# boardBase2.net
KiCad netlist of a schematic drawn in EAGLE
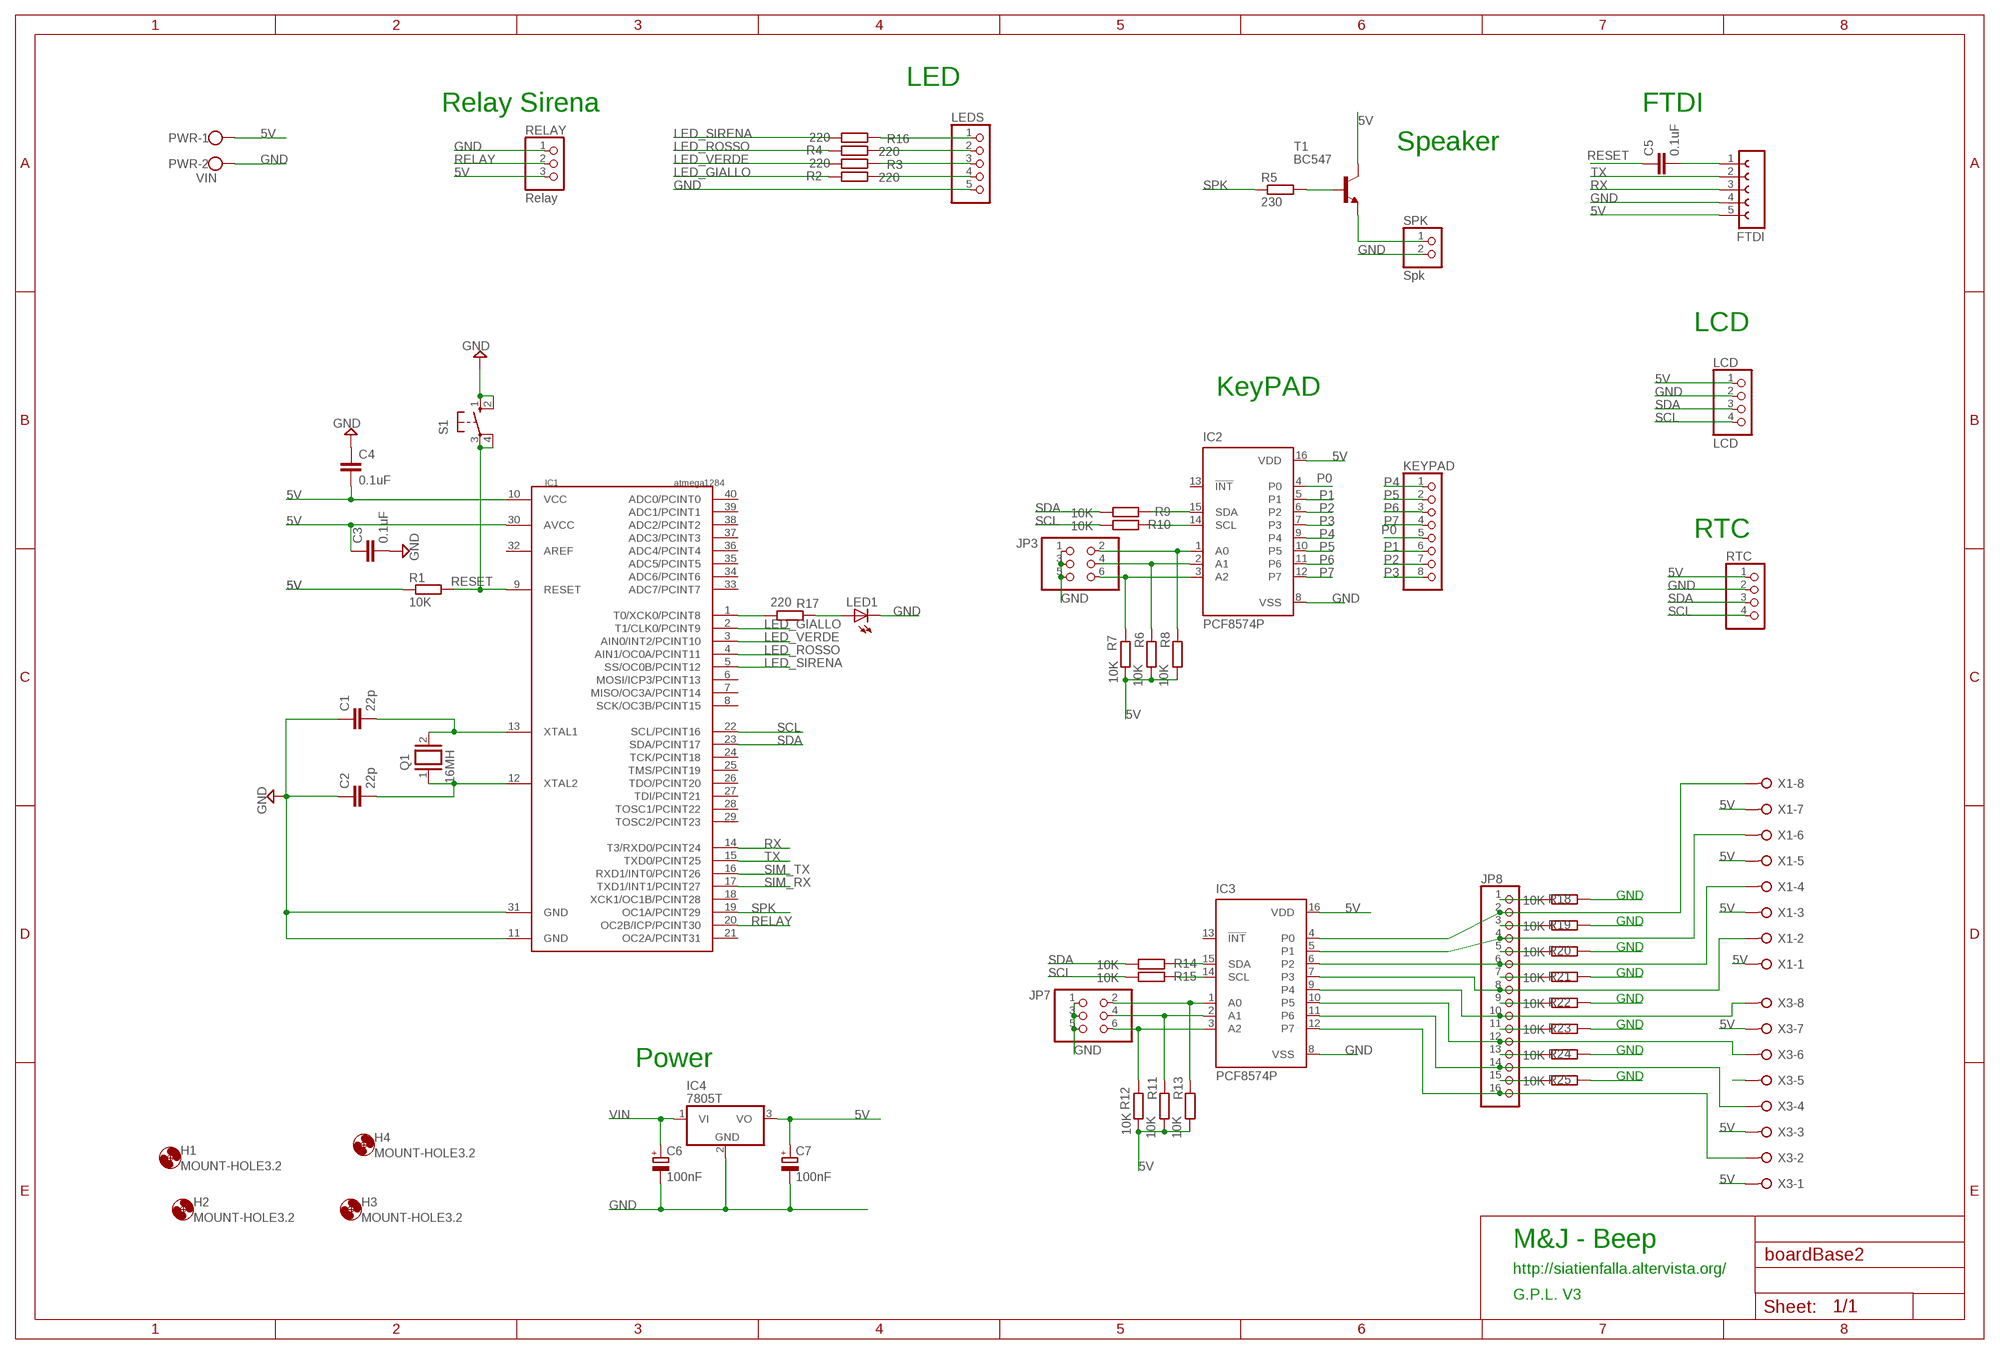
[diagram p0: schematic, sheet 1]

(export (version "E")
  (design (tool "Eeschema 10.0.6"))
  (components
    (comp (ref "C1")
      (value "22p")
      (footprint "eagle-import:C025-024X044")
      (libsource (lib "eagle-import") (part "C-EU025-024X044"))
    )
    (comp (ref "C2")
      (value "22p")
      (footprint "eagle-import:C025-024X044")
      (libsource (lib "eagle-import") (part "C-EU025-024X044"))
    )
    (comp (ref "C3")
      (value "0.1uF")
      (footprint "eagle-import:C025-025X050")
      (libsource (lib "eagle-import") (part "C-EU025-025X050"))
    )
    (comp (ref "C4")
      (value "0.1uF")
      (footprint "eagle-import:C025-025X050")
      (libsource (lib "eagle-import") (part "C-EU025-025X050"))
    )
    (comp (ref "C5")
      (value "0.1uF")
      (footprint "eagle-import:C025-025X050")
      (libsource (lib "eagle-import") (part "C-EU025-025X050"))
    )
    (comp (ref "C6")
      (value "100nF")
      (footprint "eagle-import:E3,5-10")
      (libsource (lib "eagle-import") (part "CPOL-EUE3.5-10"))
    )
    (comp (ref "C7")
      (value "100nF")
      (footprint "eagle-import:E3,5-10")
      (libsource (lib "eagle-import") (part "CPOL-EUE3.5-10"))
    )
    (comp (ref "FTDI")
      (value "FE05-1")
      (footprint "eagle-import:FE05-1")
      (libsource (lib "eagle-import") (part "FE05-1"))
    )
    (comp (ref "H1")
      (value "MOUNT-HOLE3.2")
      (footprint "eagle-import:3,2")
      (libsource (lib "eagle-import") (part "MOUNT-HOLE3.2"))
    )
    (comp (ref "H2")
      (value "MOUNT-HOLE3.2")
      (footprint "eagle-import:3,2")
      (libsource (lib "eagle-import") (part "MOUNT-HOLE3.2"))
    )
    (comp (ref "H3")
      (value "MOUNT-HOLE3.2")
      (footprint "eagle-import:3,2")
      (libsource (lib "eagle-import") (part "MOUNT-HOLE3.2"))
    )
    (comp (ref "H4")
      (value "MOUNT-HOLE3.2")
      (footprint "eagle-import:3,2")
      (libsource (lib "eagle-import") (part "MOUNT-HOLE3.2"))
    )
    (comp (ref "IC1")
      (value "atmega1284")
      (footprint "eagle-import:DIL40")
      (libsource (lib "eagle-import") (part "MEGA1284P"))
    )
    (comp (ref "IC2")
      (value "PCF8574P")
      (footprint "eagle-import:DIL16")
      (fields (field (name "MPN") "PCF8574PN"))
      (libsource (lib "eagle-import") (part "PCF8574P"))
    )
    (comp (ref "IC3")
      (value "PCF8574P")
      (footprint "eagle-import:DIL16")
      (fields (field (name "MPN") "PCF8574PN"))
      (libsource (lib "eagle-import") (part "PCF8574P"))
    )
    (comp (ref "IC4")
      (value "7805T")
      (footprint "eagle-import:TO220H")
      (libsource (lib "eagle-import") (part "78T05"))
    )
    (comp (ref "JP3")
      (value "PINHD-2X3")
      (footprint "eagle-import:2X03")
      (libsource (lib "eagle-import") (part "PINHD-2X3"))
    )
    (comp (ref "JP7")
      (value "PINHD-2X3")
      (footprint "eagle-import:2X03")
      (libsource (lib "eagle-import") (part "PINHD-2X3"))
    )
    (comp (ref "JP8")
      (value "PINHD-1X16")
      (footprint "eagle-import:1X16")
      (libsource (lib "eagle-import") (part "PINHD-1X16"))
    )
    (comp (ref "KEYPAD")
      (value "PINHD-1X8")
      (footprint "eagle-import:1X08")
      (libsource (lib "eagle-import") (part "PINHD-1X8"))
    )
    (comp (ref "LCD")
      (value "LCD")
      (footprint "eagle-import:1X04")
      (libsource (lib "eagle-import") (part "PINHD-1X4"))
    )
    (comp (ref "LED1")
      (value "LED3MM")
      (footprint "eagle-import:LED3MM")
      (libsource (lib "eagle-import") (part "LED3MM"))
    )
    (comp (ref "LEDS")
      (value "PINHD-1X5")
      (footprint "eagle-import:1X05")
      (libsource (lib "eagle-import") (part "PINHD-1X5"))
    )
    (comp (ref "PWR")
      (value "VIN")
      (footprint "eagle-import:W237-102")
      (fields (field (name "MPN") "237-102"))
      (libsource (lib "eagle-import") (part "W237-102"))
    )
    (comp (ref "Q1")
      (value "16MH")
      (footprint "eagle-import:QS")
      (libsource (lib "eagle-import") (part "XTAL/S"))
    )
    (comp (ref "R1")
      (value "10K")
      (footprint "eagle-import:0207_10")
      (libsource (lib "eagle-import") (part "R-EU_0207/10"))
    )
    (comp (ref "R2")
      (value "220")
      (footprint "eagle-import:0207_2V")
      (libsource (lib "eagle-import") (part "R-EU_0207/2V"))
    )
    (comp (ref "R3")
      (value "220")
      (footprint "eagle-import:0207_2V")
      (libsource (lib "eagle-import") (part "R-EU_0207/2V"))
    )
    (comp (ref "R4")
      (value "220")
      (footprint "eagle-import:0207_2V")
      (libsource (lib "eagle-import") (part "R-EU_0207/2V"))
    )
    (comp (ref "R5")
      (value "230")
      (footprint "eagle-import:0207_10")
      (libsource (lib "eagle-import") (part "R-EU_0207/10"))
    )
    (comp (ref "R6")
      (value "10K")
      (footprint "eagle-import:0207_10")
      (libsource (lib "eagle-import") (part "R-EU_0207/10"))
    )
    (comp (ref "R7")
      (value "10K")
      (footprint "eagle-import:0207_10")
      (libsource (lib "eagle-import") (part "R-EU_0207/10"))
    )
    (comp (ref "R8")
      (value "10K")
      (footprint "eagle-import:0207_10")
      (libsource (lib "eagle-import") (part "R-EU_0207/10"))
    )
    (comp (ref "R9")
      (value "10K")
      (footprint "eagle-import:0207_10")
      (libsource (lib "eagle-import") (part "R-EU_0207/10"))
    )
    (comp (ref "R10")
      (value "10K")
      (footprint "eagle-import:0207_10")
      (libsource (lib "eagle-import") (part "R-EU_0207/10"))
    )
    (comp (ref "R11")
      (value "10K")
      (footprint "eagle-import:0207_2V")
      (libsource (lib "eagle-import") (part "R-EU_0207/2V"))
    )
    (comp (ref "R12")
      (value "10K")
      (footprint "eagle-import:0207_2V")
      (libsource (lib "eagle-import") (part "R-EU_0207/2V"))
    )
    (comp (ref "R13")
      (value "10K")
      (footprint "eagle-import:0207_2V")
      (libsource (lib "eagle-import") (part "R-EU_0207/2V"))
    )
    (comp (ref "R14")
      (value "10K")
      (footprint "eagle-import:0207_2V")
      (libsource (lib "eagle-import") (part "R-EU_0207/2V"))
    )
    (comp (ref "R15")
      (value "10K")
      (footprint "eagle-import:0207_2V")
      (libsource (lib "eagle-import") (part "R-EU_0207/2V"))
    )
    (comp (ref "R16")
      (value "220")
      (footprint "eagle-import:0207_2V")
      (libsource (lib "eagle-import") (part "R-EU_0207/2V"))
    )
    (comp (ref "R17")
      (value "220")
      (footprint "eagle-import:0207_2V")
      (libsource (lib "eagle-import") (part "R-EU_0207/2V"))
    )
    (comp (ref "R18")
      (value "10K")
      (footprint "eagle-import:0207_2V")
      (libsource (lib "eagle-import") (part "R-EU_0207/2V"))
    )
    (comp (ref "R19")
      (value "10K")
      (footprint "eagle-import:0207_2V")
      (libsource (lib "eagle-import") (part "R-EU_0207/2V"))
    )
    (comp (ref "R20")
      (value "10K")
      (footprint "eagle-import:0207_2V")
      (libsource (lib "eagle-import") (part "R-EU_0207/2V"))
    )
    (comp (ref "R21")
      (value "10K")
      (footprint "eagle-import:0207_2V")
      (libsource (lib "eagle-import") (part "R-EU_0207/2V"))
    )
    (comp (ref "R22")
      (value "10K")
      (footprint "eagle-import:0207_2V")
      (libsource (lib "eagle-import") (part "R-EU_0207/2V"))
    )
    (comp (ref "R23")
      (value "10K")
      (footprint "eagle-import:0207_2V")
      (libsource (lib "eagle-import") (part "R-EU_0207/2V"))
    )
    (comp (ref "R24")
      (value "10K")
      (footprint "eagle-import:0207_2V")
      (libsource (lib "eagle-import") (part "R-EU_0207/2V"))
    )
    (comp (ref "R25")
      (value "10K")
      (footprint "eagle-import:0207_2V")
      (libsource (lib "eagle-import") (part "R-EU_0207/2V"))
    )
    (comp (ref "RELAY")
      (value "Relay")
      (footprint "eagle-import:1X03")
      (libsource (lib "eagle-import") (part "PINHD-1X3"))
    )
    (comp (ref "RTC")
      (value "PINHD-1X4")
      (footprint "eagle-import:1X04")
      (libsource (lib "eagle-import") (part "PINHD-1X4"))
    )
    (comp (ref "S1")
      (value "10-XX")
      (footprint "eagle-import:B3F-10XX")
      (fields (field (name "MPN") "B3F-1000"))
      (libsource (lib "eagle-import") (part "10-XX"))
    )
    (comp (ref "SPK")
      (value "Spk")
      (footprint "eagle-import:1X02")
      (libsource (lib "eagle-import") (part "PINHD-1X2"))
    )
    (comp (ref "T1")
      (value "BC547")
      (footprint "eagle-import:TO92")
      (libsource (lib "eagle-import") (part "BC547"))
    )
    (comp (ref "X1")
      (value "W237-08P")
      (footprint "eagle-import:W237-8P")
      (libsource (lib "eagle-import") (part "W237-08P"))
    )
    (comp (ref "X3")
      (value "W237-08P")
      (footprint "eagle-import:W237-8P")
      (libsource (lib "eagle-import") (part "W237-08P"))
    )
  )
  (nets
    (net (code "1") (name "/5V") (class "Default")
      (node (ref "C3") (pin "1") (pinfunction "1_1") (pintype "passive"))
      (node (ref "C4") (pin "2") (pinfunction "2_2") (pintype "passive"))
      (node (ref "C7") (pin "+") (pinfunction "+_+") (pintype "passive"))
      (node (ref "FTDI") (pin "5") (pinfunction "5_5") (pintype "passive"))
      (node (ref "IC1") (pin "10") (pinfunction "VCC_10") (pintype "bidirectional"))
      (node (ref "IC1") (pin "30") (pinfunction "AVCC_30") (pintype "bidirectional"))
      (node (ref "IC2") (pin "16") (pinfunction "VDD_16") (pintype "power_in"))
      (node (ref "IC3") (pin "16") (pinfunction "VDD_16") (pintype "power_in"))
      (node (ref "IC4") (pin "3") (pinfunction "VO_3") (pintype "passive"))
      (node (ref "LCD") (pin "1") (pinfunction "1_1") (pintype "passive"))
      (node (ref "PWR") (pin "1") (pinfunction "KL_1") (pintype "passive"))
      (node (ref "R1") (pin "1") (pinfunction "1_1") (pintype "passive"))
      (node (ref "R11") (pin "1") (pinfunction "1_1") (pintype "passive"))
      (node (ref "R12") (pin "2") (pinfunction "2_2") (pintype "passive"))
      (node (ref "R13") (pin "1") (pinfunction "1_1") (pintype "passive"))
      (node (ref "R6") (pin "1") (pinfunction "1_1") (pintype "passive"))
      (node (ref "R7") (pin "2") (pinfunction "2_2") (pintype "passive"))
      (node (ref "R8") (pin "1") (pinfunction "1_1") (pintype "passive"))
      (node (ref "RELAY") (pin "3") (pinfunction "3_3") (pintype "passive"))
      (node (ref "RTC") (pin "1") (pinfunction "1_1") (pintype "passive"))
      (node (ref "T1") (pin "3") (pinfunction "C_3") (pintype "passive"))
      (node (ref "X1") (pin "1") (pinfunction "KL_1") (pintype "passive"))
      (node (ref "X1") (pin "3") (pinfunction "KL_3") (pintype "passive"))
      (node (ref "X1") (pin "5") (pinfunction "KL_5") (pintype "passive"))
      (node (ref "X1") (pin "7") (pinfunction "KL_7") (pintype "passive"))
      (node (ref "X3") (pin "1") (pinfunction "KL_1") (pintype "passive"))
      (node (ref "X3") (pin "3") (pinfunction "KL_3") (pintype "passive"))
      (node (ref "X3") (pin "5") (pinfunction "KL_5") (pintype "passive"))
      (node (ref "X3") (pin "7") (pinfunction "KL_7") (pintype "passive"))
    )
    (net (code "2") (name "/LED_GIALLO") (class "Default")
      (node (ref "IC1") (pin "2") (pinfunction "T1/CLK0/PCINT9_2") (pintype "bidirectional"))
      (node (ref "R2") (pin "2") (pinfunction "2_2") (pintype "passive"))
    )
    (net (code "3") (name "/LED_ROSSO") (class "Default")
      (node (ref "IC1") (pin "4") (pinfunction "AIN1/OC0A/PCINT11_4") (pintype "bidirectional"))
      (node (ref "R4") (pin "2") (pinfunction "2_2") (pintype "passive"))
    )
    (net (code "4") (name "/LED_SIRENA") (class "Default")
      (node (ref "IC1") (pin "5") (pinfunction "SS/OC0B/PCINT12_5") (pintype "bidirectional"))
      (node (ref "R16") (pin "1") (pinfunction "1_1") (pintype "passive"))
    )
    (net (code "5") (name "/LED_VERDE") (class "Default")
      (node (ref "IC1") (pin "3") (pinfunction "AIN0/INT2/PCINT10_3") (pintype "bidirectional"))
      (node (ref "R3") (pin "1") (pinfunction "1_1") (pintype "passive"))
    )
    (net (code "6") (name "/P0") (class "Default")
      (node (ref "IC2") (pin "4") (pinfunction "P0_4") (pintype "bidirectional"))
      (node (ref "KEYPAD") (pin "5") (pinfunction "5_5") (pintype "passive"))
    )
    (net (code "7") (name "/P1") (class "Default")
      (node (ref "IC2") (pin "5") (pinfunction "P1_5") (pintype "bidirectional"))
      (node (ref "KEYPAD") (pin "6") (pinfunction "6_6") (pintype "passive"))
    )
    (net (code "8") (name "/P2") (class "Default")
      (node (ref "IC2") (pin "6") (pinfunction "P2_6") (pintype "bidirectional"))
      (node (ref "KEYPAD") (pin "7") (pinfunction "7_7") (pintype "passive"))
    )
    (net (code "9") (name "/P3") (class "Default")
      (node (ref "IC2") (pin "7") (pinfunction "P3_7") (pintype "bidirectional"))
      (node (ref "KEYPAD") (pin "8") (pinfunction "8_8") (pintype "passive"))
    )
    (net (code "10") (name "/P4") (class "Default")
      (node (ref "IC2") (pin "9") (pinfunction "P4_9") (pintype "bidirectional"))
      (node (ref "KEYPAD") (pin "1") (pinfunction "1_1") (pintype "passive"))
    )
    (net (code "11") (name "/P5") (class "Default")
      (node (ref "IC2") (pin "10") (pinfunction "P5_10") (pintype "bidirectional"))
      (node (ref "KEYPAD") (pin "2") (pinfunction "2_2") (pintype "passive"))
    )
    (net (code "12") (name "/P6") (class "Default")
      (node (ref "IC2") (pin "11") (pinfunction "P6_11") (pintype "bidirectional"))
      (node (ref "KEYPAD") (pin "3") (pinfunction "3_3") (pintype "passive"))
    )
    (net (code "13") (name "/P7") (class "Default")
      (node (ref "IC2") (pin "12") (pinfunction "P7_12") (pintype "bidirectional"))
      (node (ref "KEYPAD") (pin "4") (pinfunction "4_4") (pintype "passive"))
    )
    (net (code "14") (name "/RELAY") (class "Default")
      (node (ref "IC1") (pin "20") (pinfunction "OC2B/ICP/PCINT30_20") (pintype "bidirectional"))
      (node (ref "RELAY") (pin "2") (pinfunction "2_2") (pintype "passive"))
    )
    (net (code "15") (name "/RESET") (class "Default")
      (node (ref "C5") (pin "1") (pinfunction "1_1") (pintype "passive"))
      (node (ref "IC1") (pin "9") (pinfunction "RESET_9") (pintype "bidirectional"))
      (node (ref "R1") (pin "2") (pinfunction "2_2") (pintype "passive"))
      (node (ref "S1") (pin "3") (pinfunction "P_3") (pintype "passive"))
      (node (ref "S1") (pin "4") (pinfunction "P1_4") (pintype "passive"))
    )
    (net (code "16") (name "/RX") (class "Default")
      (node (ref "FTDI") (pin "3") (pinfunction "3_3") (pintype "passive"))
      (node (ref "IC1") (pin "14") (pinfunction "T3/RXD0/PCINT24_14") (pintype "bidirectional"))
    )
    (net (code "17") (name "/SCL") (class "Default")
      (node (ref "IC1") (pin "22") (pinfunction "SCL/PCINT16_22") (pintype "bidirectional"))
      (node (ref "LCD") (pin "4") (pinfunction "4_4") (pintype "passive"))
      (node (ref "R10") (pin "2") (pinfunction "2_2") (pintype "passive"))
      (node (ref "R15") (pin "2") (pinfunction "2_2") (pintype "passive"))
      (node (ref "RTC") (pin "4") (pinfunction "4_4") (pintype "passive"))
    )
    (net (code "18") (name "/SDA") (class "Default")
      (node (ref "IC1") (pin "23") (pinfunction "SDA/PCINT17_23") (pintype "bidirectional"))
      (node (ref "LCD") (pin "3") (pinfunction "3_3") (pintype "passive"))
      (node (ref "R14") (pin "2") (pinfunction "2_2") (pintype "passive"))
      (node (ref "R9") (pin "2") (pinfunction "2_2") (pintype "passive"))
      (node (ref "RTC") (pin "3") (pinfunction "3_3") (pintype "passive"))
    )
    (net (code "19") (name "/SIM_RX") (class "Default")
      (node (ref "IC1") (pin "17") (pinfunction "TXD1/INT1/PCINT27_17") (pintype "bidirectional"))
    )
    (net (code "20") (name "/SIM_TX") (class "Default")
      (node (ref "IC1") (pin "16") (pinfunction "RXD1/INT0/PCINT26_16") (pintype "bidirectional"))
    )
    (net (code "21") (name "/SPK") (class "Default")
      (node (ref "IC1") (pin "19") (pinfunction "OC1A/PCINT29_19") (pintype "bidirectional"))
      (node (ref "R5") (pin "1") (pinfunction "1_1") (pintype "passive"))
    )
    (net (code "22") (name "/TX") (class "Default")
      (node (ref "FTDI") (pin "2") (pinfunction "2_2") (pintype "passive"))
      (node (ref "IC1") (pin "15") (pinfunction "TXD0/PCINT25_15") (pintype "bidirectional"))
    )
    (net (code "23") (name "/VIN") (class "Default")
      (node (ref "C6") (pin "+") (pinfunction "+_+") (pintype "passive"))
      (node (ref "IC4") (pin "1") (pinfunction "VI_1") (pintype "input"))
    )
    (net (code "24") (name "GND") (class "Default")
      (node (ref "C1") (pin "1") (pinfunction "1_1") (pintype "passive"))
      (node (ref "C2") (pin "1") (pinfunction "1_1") (pintype "passive"))
      (node (ref "C3") (pin "2") (pinfunction "2_2") (pintype "passive"))
      (node (ref "C4") (pin "1") (pinfunction "1_1") (pintype "passive"))
      (node (ref "C6") (pin "-") (pinfunction "-_-") (pintype "passive"))
      (node (ref "C7") (pin "-") (pinfunction "-_-") (pintype "passive"))
      (node (ref "FTDI") (pin "4") (pinfunction "4_4") (pintype "passive"))
      (node (ref "IC1") (pin "11") (pinfunction "GND_11") (pintype "bidirectional"))
      (node (ref "IC1") (pin "31") (pinfunction "GND_31") (pintype "bidirectional"))
      (node (ref "IC2") (pin "8") (pinfunction "VSS_8") (pintype "power_in"))
      (node (ref "IC3") (pin "8") (pinfunction "VSS_8") (pintype "power_in"))
      (node (ref "IC4") (pin "2") (pinfunction "GND_2") (pintype "passive"))
      (node (ref "JP3") (pin "1") (pinfunction "1_1") (pintype "passive"))
      (node (ref "JP3") (pin "3") (pinfunction "3_3") (pintype "passive"))
      (node (ref "JP3") (pin "5") (pinfunction "5_5") (pintype "passive"))
      (node (ref "JP7") (pin "1") (pinfunction "1_1") (pintype "passive"))
      (node (ref "JP7") (pin "3") (pinfunction "3_3") (pintype "passive"))
      (node (ref "JP7") (pin "5") (pinfunction "5_5") (pintype "passive"))
      (node (ref "LCD") (pin "2") (pinfunction "2_2") (pintype "passive"))
      (node (ref "LED1") (pin "K") (pinfunction "C_K") (pintype "passive"))
      (node (ref "LEDS") (pin "5") (pinfunction "5_5") (pintype "passive"))
      (node (ref "PWR") (pin "2") (pinfunction "KL_2") (pintype "passive"))
      (node (ref "R18") (pin "1") (pinfunction "1_1") (pintype "passive"))
      (node (ref "R19") (pin "1") (pinfunction "1_1") (pintype "passive"))
      (node (ref "R21") (pin "1") (pinfunction "1_1") (pintype "passive"))
      (node (ref "R22") (pin "1") (pinfunction "1_1") (pintype "passive"))
      (node (ref "R23") (pin "1") (pinfunction "1_1") (pintype "passive"))
      (node (ref "R24") (pin "1") (pinfunction "1_1") (pintype "passive"))
      (node (ref "R25") (pin "1") (pinfunction "1_1") (pintype "passive"))
      (node (ref "RELAY") (pin "1") (pinfunction "1_1") (pintype "passive"))
      (node (ref "RTC") (pin "2") (pinfunction "2_2") (pintype "passive"))
      (node (ref "S1") (pin "1") (pinfunction "S_1") (pintype "passive"))
      (node (ref "S1") (pin "2") (pinfunction "S1_2") (pintype "passive"))
      (node (ref "SPK") (pin "2") (pinfunction "2_2") (pintype "passive"))
    )
    (net (code "25") (name "Net-(C5-Pad2)") (class "Default")
      (node (ref "C5") (pin "2") (pinfunction "2_2") (pintype "passive"))
      (node (ref "FTDI") (pin "1") (pinfunction "1_1") (pintype "passive"))
    )
    (net (code "26") (name "Net-(IC1-T0{slash}XCK0{slash}PCINT8)") (class "Default")
      (node (ref "IC1") (pin "1") (pinfunction "T0/XCK0/PCINT8_1") (pintype "bidirectional"))
      (node (ref "R17") (pin "1") (pinfunction "1_1") (pintype "passive"))
    )
    (net (code "27") (name "Net-(IC1-XTAL1)") (class "Default")
      (node (ref "C1") (pin "2") (pinfunction "2_2") (pintype "passive"))
      (node (ref "IC1") (pin "13") (pinfunction "XTAL1_13") (pintype "bidirectional"))
      (node (ref "Q1") (pin "2") (pinfunction "2_2") (pintype "passive"))
    )
    (net (code "28") (name "Net-(IC1-XTAL2)") (class "Default")
      (node (ref "C2") (pin "2") (pinfunction "2_2") (pintype "passive"))
      (node (ref "IC1") (pin "12") (pinfunction "XTAL2_12") (pintype "bidirectional"))
      (node (ref "Q1") (pin "1") (pinfunction "1_1") (pintype "passive"))
    )
    (net (code "29") (name "Net-(IC2-A0)") (class "Default")
      (node (ref "IC2") (pin "1") (pinfunction "A0_1") (pintype "input"))
      (node (ref "JP3") (pin "2") (pinfunction "2_2") (pintype "passive"))
      (node (ref "R8") (pin "2") (pinfunction "2_2") (pintype "passive"))
    )
    (net (code "30") (name "Net-(IC2-A1)") (class "Default")
      (node (ref "IC2") (pin "2") (pinfunction "A1_2") (pintype "input"))
      (node (ref "JP3") (pin "4") (pinfunction "4_4") (pintype "passive"))
      (node (ref "R6") (pin "2") (pinfunction "2_2") (pintype "passive"))
    )
    (net (code "31") (name "Net-(IC2-A2)") (class "Default")
      (node (ref "IC2") (pin "3") (pinfunction "A2_3") (pintype "input"))
      (node (ref "JP3") (pin "6") (pinfunction "6_6") (pintype "passive"))
      (node (ref "R7") (pin "1") (pinfunction "1_1") (pintype "passive"))
    )
    (net (code "32") (name "Net-(IC2-SCL)") (class "Default")
      (node (ref "IC2") (pin "14") (pinfunction "SCL_14") (pintype "input"))
      (node (ref "R10") (pin "1") (pinfunction "1_1") (pintype "passive"))
    )
    (net (code "33") (name "Net-(IC2-SDA)") (class "Default")
      (node (ref "IC2") (pin "15") (pinfunction "SDA_15") (pintype "bidirectional"))
      (node (ref "R9") (pin "1") (pinfunction "1_1") (pintype "passive"))
    )
    (net (code "34") (name "Net-(IC3-A0)") (class "Default")
      (node (ref "IC3") (pin "1") (pinfunction "A0_1") (pintype "input"))
      (node (ref "JP7") (pin "2") (pinfunction "2_2") (pintype "passive"))
      (node (ref "R13") (pin "2") (pinfunction "2_2") (pintype "passive"))
    )
    (net (code "35") (name "Net-(IC3-A1)") (class "Default")
      (node (ref "IC3") (pin "2") (pinfunction "A1_2") (pintype "input"))
      (node (ref "JP7") (pin "4") (pinfunction "4_4") (pintype "passive"))
      (node (ref "R11") (pin "2") (pinfunction "2_2") (pintype "passive"))
    )
    (net (code "36") (name "Net-(IC3-A2)") (class "Default")
      (node (ref "IC3") (pin "3") (pinfunction "A2_3") (pintype "input"))
      (node (ref "JP7") (pin "6") (pinfunction "6_6") (pintype "passive"))
      (node (ref "R12") (pin "1") (pinfunction "1_1") (pintype "passive"))
    )
    (net (code "37") (name "Net-(IC3-P0)") (class "Default")
      (node (ref "IC3") (pin "4") (pinfunction "P0_4") (pintype "bidirectional"))
      (node (ref "JP8") (pin "2") (pinfunction "2_2") (pintype "passive"))
      (node (ref "X1") (pin "8") (pinfunction "KL_8") (pintype "passive"))
    )
    (net (code "38") (name "Net-(IC3-P1)") (class "Default")
      (node (ref "IC3") (pin "5") (pinfunction "P1_5") (pintype "bidirectional"))
      (node (ref "JP8") (pin "4") (pinfunction "4_4") (pintype "passive"))
      (node (ref "X1") (pin "6") (pinfunction "KL_6") (pintype "passive"))
    )
    (net (code "39") (name "Net-(IC3-P2)") (class "Default")
      (node (ref "IC3") (pin "6") (pinfunction "P2_6") (pintype "bidirectional"))
      (node (ref "JP8") (pin "6") (pinfunction "6_6") (pintype "passive"))
      (node (ref "X1") (pin "4") (pinfunction "KL_4") (pintype "passive"))
    )
    (net (code "40") (name "Net-(IC3-P3)") (class "Default")
      (node (ref "IC3") (pin "7") (pinfunction "P3_7") (pintype "bidirectional"))
      (node (ref "JP8") (pin "8") (pinfunction "8_8") (pintype "passive"))
      (node (ref "X1") (pin "2") (pinfunction "KL_2") (pintype "passive"))
    )
    (net (code "41") (name "Net-(IC3-P4)") (class "Default")
      (node (ref "IC3") (pin "9") (pinfunction "P4_9") (pintype "bidirectional"))
      (node (ref "JP8") (pin "10") (pinfunction "10_10") (pintype "passive"))
      (node (ref "X3") (pin "8") (pinfunction "KL_8") (pintype "passive"))
    )
    (net (code "42") (name "Net-(IC3-P5)") (class "Default")
      (node (ref "IC3") (pin "10") (pinfunction "P5_10") (pintype "bidirectional"))
      (node (ref "JP8") (pin "12") (pinfunction "12_12") (pintype "passive"))
      (node (ref "X3") (pin "6") (pinfunction "KL_6") (pintype "passive"))
    )
    (net (code "43") (name "Net-(IC3-P6)") (class "Default")
      (node (ref "IC3") (pin "11") (pinfunction "P6_11") (pintype "bidirectional"))
      (node (ref "JP8") (pin "14") (pinfunction "14_14") (pintype "passive"))
      (node (ref "X3") (pin "4") (pinfunction "KL_4") (pintype "passive"))
    )
    (net (code "44") (name "Net-(IC3-P7)") (class "Default")
      (node (ref "IC3") (pin "12") (pinfunction "P7_12") (pintype "bidirectional"))
      (node (ref "JP8") (pin "16") (pinfunction "16_16") (pintype "passive"))
      (node (ref "X3") (pin "2") (pinfunction "KL_2") (pintype "passive"))
    )
    (net (code "45") (name "Net-(IC3-SCL)") (class "Default")
      (node (ref "IC3") (pin "14") (pinfunction "SCL_14") (pintype "input"))
      (node (ref "R15") (pin "1") (pinfunction "1_1") (pintype "passive"))
    )
    (net (code "46") (name "Net-(IC3-SDA)") (class "Default")
      (node (ref "IC3") (pin "15") (pinfunction "SDA_15") (pintype "bidirectional"))
      (node (ref "R14") (pin "1") (pinfunction "1_1") (pintype "passive"))
    )
    (net (code "47") (name "Net-(JP8-Pad1)") (class "Default")
      (node (ref "JP8") (pin "1") (pinfunction "1_1") (pintype "passive"))
      (node (ref "R18") (pin "2") (pinfunction "2_2") (pintype "passive"))
    )
    (net (code "48") (name "Net-(JP8-Pad3)") (class "Default")
      (node (ref "JP8") (pin "3") (pinfunction "3_3") (pintype "passive"))
      (node (ref "R19") (pin "2") (pinfunction "2_2") (pintype "passive"))
    )
    (net (code "49") (name "Net-(JP8-Pad5)") (class "Default")
      (node (ref "JP8") (pin "5") (pinfunction "5_5") (pintype "passive"))
      (node (ref "R20") (pin "2") (pinfunction "2_2") (pintype "passive"))
    )
    (net (code "50") (name "Net-(JP8-Pad7)") (class "Default")
      (node (ref "JP8") (pin "7") (pinfunction "7_7") (pintype "passive"))
      (node (ref "R21") (pin "2") (pinfunction "2_2") (pintype "passive"))
    )
    (net (code "51") (name "Net-(JP8-Pad9)") (class "Default")
      (node (ref "JP8") (pin "9") (pinfunction "9_9") (pintype "passive"))
      (node (ref "R22") (pin "2") (pinfunction "2_2") (pintype "passive"))
    )
    (net (code "52") (name "Net-(JP8-Pad11)") (class "Default")
      (node (ref "JP8") (pin "11") (pinfunction "11_11") (pintype "passive"))
      (node (ref "R23") (pin "2") (pinfunction "2_2") (pintype "passive"))
    )
    (net (code "53") (name "Net-(JP8-Pad13)") (class "Default")
      (node (ref "JP8") (pin "13") (pinfunction "13_13") (pintype "passive"))
      (node (ref "R24") (pin "2") (pinfunction "2_2") (pintype "passive"))
    )
    (net (code "54") (name "Net-(JP8-Pad15)") (class "Default")
      (node (ref "JP8") (pin "15") (pinfunction "15_15") (pintype "passive"))
      (node (ref "R25") (pin "2") (pinfunction "2_2") (pintype "passive"))
    )
    (net (code "55") (name "Net-(LED1-PadA)") (class "Default")
      (node (ref "LED1") (pin "A") (pinfunction "A_A") (pintype "passive"))
      (node (ref "R17") (pin "2") (pinfunction "2_2") (pintype "passive"))
    )
    (net (code "56") (name "Net-(LEDS-Pad1)") (class "Default")
      (node (ref "LEDS") (pin "1") (pinfunction "1_1") (pintype "passive"))
      (node (ref "R16") (pin "2") (pinfunction "2_2") (pintype "passive"))
    )
    (net (code "57") (name "Net-(LEDS-Pad2)") (class "Default")
      (node (ref "LEDS") (pin "2") (pinfunction "2_2") (pintype "passive"))
      (node (ref "R4") (pin "1") (pinfunction "1_1") (pintype "passive"))
    )
    (net (code "58") (name "Net-(LEDS-Pad3)") (class "Default")
      (node (ref "LEDS") (pin "3") (pinfunction "3_3") (pintype "passive"))
      (node (ref "R3") (pin "2") (pinfunction "2_2") (pintype "passive"))
    )
    (net (code "59") (name "Net-(LEDS-Pad4)") (class "Default")
      (node (ref "LEDS") (pin "4") (pinfunction "4_4") (pintype "passive"))
      (node (ref "R2") (pin "1") (pinfunction "1_1") (pintype "passive"))
    )
    (net (code "60") (name "Net-(T1-B)") (class "Default")
      (node (ref "R5") (pin "2") (pinfunction "2_2") (pintype "passive"))
      (node (ref "T1") (pin "2") (pinfunction "B_2") (pintype "passive"))
    )
    (net (code "61") (name "Net-(T1-E)") (class "Default")
      (node (ref "SPK") (pin "1") (pinfunction "1_1") (pintype "passive"))
      (node (ref "T1") (pin "1") (pinfunction "E_1") (pintype "passive"))
    )
    (net (code "62") (name "unconnected-(IC1-ADC0{slash}PCINT0-Pad40)") (class "Default")
      (node (ref "IC1") (pin "40") (pinfunction "ADC0/PCINT0_40") (pintype "bidirectional"))
    )
    (net (code "63") (name "unconnected-(IC1-ADC1{slash}PCINT1-Pad39)") (class "Default")
      (node (ref "IC1") (pin "39") (pinfunction "ADC1/PCINT1_39") (pintype "bidirectional"))
    )
    (net (code "64") (name "unconnected-(IC1-ADC2{slash}PCINT2-Pad38)") (class "Default")
      (node (ref "IC1") (pin "38") (pinfunction "ADC2/PCINT2_38") (pintype "bidirectional"))
    )
    (net (code "65") (name "unconnected-(IC1-ADC3{slash}PCINT3-Pad37)") (class "Default")
      (node (ref "IC1") (pin "37") (pinfunction "ADC3/PCINT3_37") (pintype "bidirectional"))
    )
    (net (code "66") (name "unconnected-(IC1-ADC4{slash}PCINT4-Pad36)") (class "Default")
      (node (ref "IC1") (pin "36") (pinfunction "ADC4/PCINT4_36") (pintype "bidirectional"))
    )
    (net (code "67") (name "unconnected-(IC1-ADC5{slash}PCINT5-Pad35)") (class "Default")
      (node (ref "IC1") (pin "35") (pinfunction "ADC5/PCINT5_35") (pintype "bidirectional"))
    )
    (net (code "68") (name "unconnected-(IC1-ADC6{slash}PCINT6-Pad34)") (class "Default")
      (node (ref "IC1") (pin "34") (pinfunction "ADC6/PCINT6_34") (pintype "bidirectional"))
    )
    (net (code "69") (name "unconnected-(IC1-ADC7{slash}PCINT7-Pad33)") (class "Default")
      (node (ref "IC1") (pin "33") (pinfunction "ADC7/PCINT7_33") (pintype "bidirectional"))
    )
    (net (code "70") (name "unconnected-(IC1-AREF-Pad32)") (class "Default")
      (node (ref "IC1") (pin "32") (pinfunction "AREF_32") (pintype "bidirectional"))
    )
    (net (code "71") (name "unconnected-(IC1-MISO{slash}OC3A{slash}PCINT14-Pad7)") (class "Default")
      (node (ref "IC1") (pin "7") (pinfunction "MISO/OC3A/PCINT14_7") (pintype "bidirectional"))
    )
    (net (code "72") (name "unconnected-(IC1-MOSI{slash}ICP3{slash}PCINT13-Pad6)") (class "Default")
      (node (ref "IC1") (pin "6") (pinfunction "MOSI/ICP3/PCINT13_6") (pintype "bidirectional"))
    )
    (net (code "73") (name "unconnected-(IC1-OC2A{slash}PCINT31-Pad21)") (class "Default")
      (node (ref "IC1") (pin "21") (pinfunction "OC2A/PCINT31_21") (pintype "bidirectional"))
    )
    (net (code "74") (name "unconnected-(IC1-SCK{slash}OC3B{slash}PCINT15-Pad8)") (class "Default")
      (node (ref "IC1") (pin "8") (pinfunction "SCK/OC3B/PCINT15_8") (pintype "bidirectional"))
    )
    (net (code "75") (name "unconnected-(IC1-TCK{slash}PCINT18-Pad24)") (class "Default")
      (node (ref "IC1") (pin "24") (pinfunction "TCK/PCINT18_24") (pintype "bidirectional"))
    )
    (net (code "76") (name "unconnected-(IC1-TDI{slash}PCINT21-Pad27)") (class "Default")
      (node (ref "IC1") (pin "27") (pinfunction "TDI/PCINT21_27") (pintype "bidirectional"))
    )
    (net (code "77") (name "unconnected-(IC1-TDO{slash}PCINT20-Pad26)") (class "Default")
      (node (ref "IC1") (pin "26") (pinfunction "TDO/PCINT20_26") (pintype "bidirectional"))
    )
    (net (code "78") (name "unconnected-(IC1-TMS{slash}PCINT19-Pad25)") (class "Default")
      (node (ref "IC1") (pin "25") (pinfunction "TMS/PCINT19_25") (pintype "bidirectional"))
    )
    (net (code "79") (name "unconnected-(IC1-TOSC1{slash}PCINT22-Pad28)") (class "Default")
      (node (ref "IC1") (pin "28") (pinfunction "TOSC1/PCINT22_28") (pintype "bidirectional"))
    )
    (net (code "80") (name "unconnected-(IC1-TOSC2{slash}PCINT23-Pad29)") (class "Default")
      (node (ref "IC1") (pin "29") (pinfunction "TOSC2/PCINT23_29") (pintype "bidirectional"))
    )
    (net (code "81") (name "unconnected-(IC1-XCK1{slash}OC1B{slash}PCINT28-Pad18)") (class "Default")
      (node (ref "IC1") (pin "18") (pinfunction "XCK1/OC1B/PCINT28_18") (pintype "bidirectional"))
    )
    (net (code "82") (name "unconnected-(IC2-~{INT}-Pad13)") (class "Default")
      (node (ref "IC2") (pin "13") (pinfunction "~{INT}_13") (pintype "output"))
    )
    (net (code "83") (name "unconnected-(IC3-~{INT}-Pad13)") (class "Default")
      (node (ref "IC3") (pin "13") (pinfunction "~{INT}_13") (pintype "output"))
    )
    (net (code "84") (name "unconnected-(R20-Pad1)") (class "Default")
      (node (ref "R20") (pin "1") (pinfunction "1_1") (pintype "passive"))
    )
  )
)
